# -20210715.net
KiCad netlist of a schematic drawn in Altium Designer
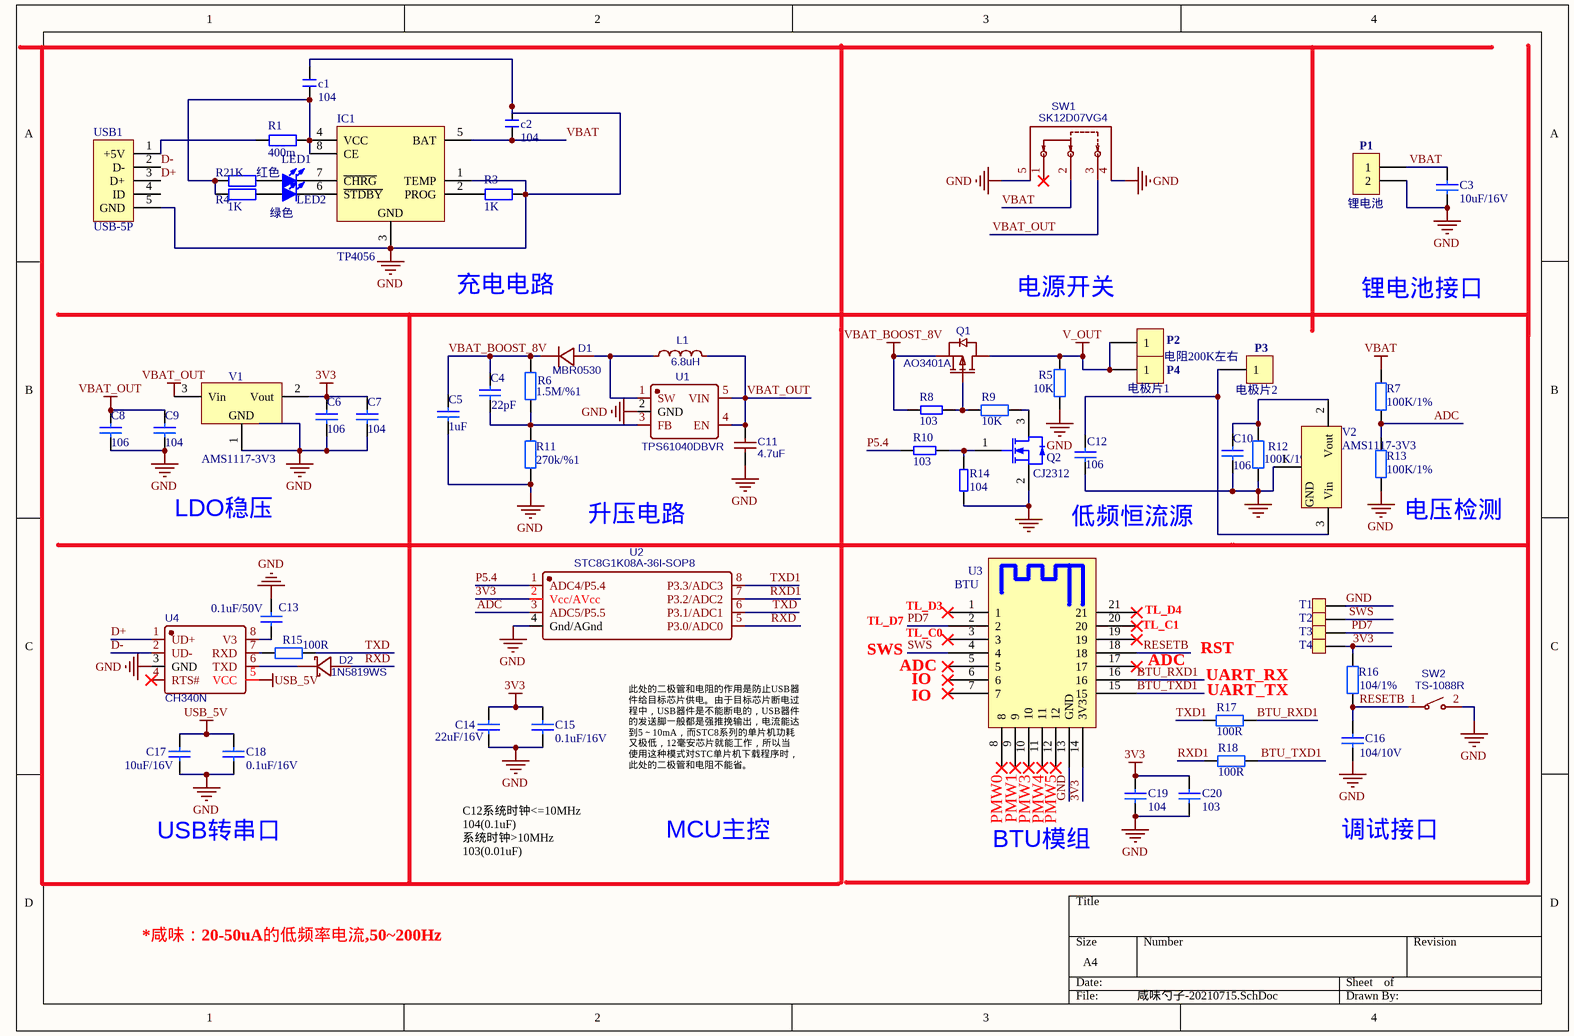
[diagram p0: 咸味勺子-20210715.SchDoc]

(export (version "E")
  (design (tool "Eeschema 10.0.6"))
  (components
    (comp (ref "c1") (value "104") (footprint "C 0805_M") (libsource (lib "Schlib1") (part "0805")))
    (comp (ref "c2") (value "104") (footprint "C 0805_M") (libsource (lib "Schlib1") (part "0805")))
    (comp (ref "C3")
      (value "10uF/16V")
      (footprint "C0603")
      (description "无极性电容")
      (fields (field (name "PART NUMBER") "1.02.05.00869"))
      (libsource (lib "Database_Libs4") (part "Capacitor - non polarized"))
    )
    (comp (ref "C4")
      (value "22pF")
      (footprint "C0402_GRM15")
      (description "无极性电容")
      (fields (field (name "PART NUMBER") "1.02.05.00869"))
      (libsource (lib "Database_Libs4") (part "Capacitor - non polarized"))
    )
    (comp (ref "C5")
      (value "1uF")
      (footprint "C0603")
      (description "无极性电容")
      (fields (field (name "PART NUMBER") "1.02.05.00869"))
      (libsource (lib "Database_Libs4") (part "Capacitor - non polarized"))
    )
    (comp (ref "C6")
      (value "106")
      (footprint "C0603")
      (description "无极性电容")
      (fields (field (name "PART NUMBER") "1.02.05.00869"))
      (libsource (lib "Database_Libs4") (part "Capacitor - non polarized"))
    )
    (comp (ref "C7")
      (value "104")
      (footprint "C0402_GRM15")
      (description "无极性电容")
      (fields (field (name "PART NUMBER") "1.02.05.00869"))
      (libsource (lib "Database_Libs4") (part "Capacitor - non polarized"))
    )
    (comp (ref "C8")
      (value "106")
      (footprint "C0603")
      (description "无极性电容")
      (fields (field (name "PART NUMBER") "1.02.05.00869"))
      (libsource (lib "Database_Libs4") (part "Capacitor - non polarized"))
    )
    (comp (ref "C9")
      (value "104")
      (footprint "C0402_GRM15")
      (description "无极性电容")
      (fields (field (name "PART NUMBER") "1.02.05.00869"))
      (libsource (lib "Database_Libs4") (part "Capacitor - non polarized"))
    )
    (comp (ref "C10")
      (value "106")
      (footprint "C0603")
      (description "无极性电容")
      (fields (field (name "PART NUMBER") "1.02.05.00869"))
      (libsource (lib "Database_Libs4") (part "Capacitor - non polarized"))
    )
    (comp (ref "C11")
      (value "4.7uF")
      (footprint "JMK212BJ475KG-T")
      (fields
        (field (name "BOM_MANUFACTURER PART") "JMK212BJ475KG-T")
        (field (name "BOM_SUPPLIER PART") "C92788")
      )
      (libsource (lib "altium-import") (part "root_1_4.7uF_"))
    )
    (comp (ref "C12")
      (value "106")
      (footprint "C0603")
      (description "无极性电容")
      (fields (field (name "PART NUMBER") "1.02.05.00869"))
      (libsource (lib "Database_Libs4") (part "Capacitor - non polarized"))
    )
    (comp (ref "C13")
      (value "0.1uF/50V")
      (footprint "C0402_GRM15")
      (description "无极性电容")
      (fields (field (name "PART NUMBER") "1.02.05.00834") (field (name "修改人") "system"))
      (libsource (lib "Database_Libs") (part "Capacitor - non polarized"))
    )
    (comp (ref "C14")
      (value "22uF/16V")
      (footprint "C0603")
      (description "无极性电容")
      (fields (field (name "PART NUMBER") "1.02.03.00181") (field (name "修改人") "system"))
      (libsource (lib "Database_Libs") (part "Capacitor - non polarized"))
    )
    (comp (ref "C15")
      (value "0.1uF/16V")
      (footprint "C0402_GRM15")
      (description "无极性电容")
      (fields (field (name "PART NUMBER") "1.02.05.00834") (field (name "修改人") "system"))
      (libsource (lib "Database_Libs") (part "Capacitor - non polarized"))
    )
    (comp (ref "C16")
      (value "104/10V")
      (footprint "C0402_GRM15")
      (description "无极性电容")
      (fields (field (name "PART NUMBER") "1.02.05.00869"))
      (libsource (lib "Database_Libs4") (part "Capacitor - non polarized"))
    )
    (comp (ref "C17")
      (value "10uF/16V")
      (footprint "C0603")
      (description "无极性电容")
      (fields (field (name "PART NUMBER") "1.02.03.00181") (field (name "修改人") "system"))
      (libsource (lib "Database_Libs") (part "Capacitor - non polarized"))
    )
    (comp (ref "C18")
      (value "0.1uF/16V")
      (footprint "C0402_GRM15")
      (description "无极性电容")
      (fields (field (name "PART NUMBER") "1.02.05.00834") (field (name "修改人") "system"))
      (libsource (lib "Database_Libs") (part "Capacitor - non polarized"))
    )
    (comp (ref "C19")
      (value "104")
      (footprint "C0402_GRM15")
      (description "无极性电容")
      (fields (field (name "PART NUMBER") "1.02.05.00869"))
      (libsource (lib "Database_Libs4") (part "Capacitor - non polarized"))
    )
    (comp (ref "C20")
      (value "103")
      (footprint "C0402_GRM15")
      (description "无极性电容")
      (fields (field (name "PART NUMBER") "1.02.05.00869"))
      (libsource (lib "Database_Libs4") (part "Capacitor - non polarized"))
    )
    (comp (ref "D1")
      (value "MBR0530")
      (footprint "MBR0530")
      (fields (field (name "BOM_SUPPLIER PART") "C475718") (field (name "CONTRIBUTOR") "LCSC"))
      (libsource (lib "altium-import") (part "root_0_MBR0530_C475718_"))
    )
    (comp (ref "D2")
      (value "1N5819WS")
      (footprint "1N5819WS")
      (fields (field (name "BOM_SUPPLIER PART") "C1884554") (field (name "CONTRIBUTOR") "LCSC"))
      (libsource (lib "altium-import") (part "root_0_1N5819WS_C1884554_"))
    )
    (comp (ref "IC1") (value "TP4056") (footprint "SOP8_M") (libsource (lib "Schlib1") (part "TP4056")))
    (comp (ref "L1")
      (value "6.8uH")
      (footprint "CDRH3D23NP-6R8PC")
      (fields
        (field (name "BOM_SUPPLIER PART") "C323532")
        (field (name "BOM_MANUFACTURER PART") "CDRH3D23NP-6R8PC")
        (field (name "CONTRIBUTOR") "LCSC")
      )
      (libsource (lib "altium-import") (part "root_0_6.8uH_"))
    )
    (comp (ref "LED1")
      (value "红色")
      (footprint "LED 0805B")
      (description "贴片LED")
      (libsource (lib "Schlib1") (part "LED-SMD"))
    )
    (comp (ref "LED2")
      (value "绿色")
      (footprint "LED 0805B")
      (description "贴片LED")
      (libsource (lib "Schlib1") (part "LED-SMD"))
    )
    (comp (ref "P1")
      (value "锂电池")
      (footprint "1.5mm 2p接插件")
      (description "Connector")
      (libsource (lib "*") (part "CON2"))
    )
    (comp (ref "P2") (value "CON1") (footprint "焊点1") (libsource (lib "智能烧水壶 -电源板") (part "CON1")))
    (comp (ref "P3") (value "CON1") (footprint "焊点1") (libsource (lib "智能烧水壶 -电源板") (part "CON1")))
    (comp (ref "P4") (value "CON1") (footprint "焊点1") (libsource (lib "智能烧水壶 -电源板") (part "CON1")))
    (comp (ref "Q1")
      (value "AO3401A")
      (footprint "AO3401A")
      (fields (field (name "BOM_SUPPLIER PART") "C700954") (field (name "CONTRIBUTOR") "LCSC"))
      (libsource (lib "altium-import") (part "root_1_mirrored_AO3401A_C700954_"))
    )
    (comp (ref "Q2")
      (value "CJ2312")
      (footprint "CJ2312")
      (description "N-Channel MOSFET")
      (fields
        (field (name "PART NUMBER") "1.06.11.00008")
        (field (name "ORCAD LIBRARY PATH") "‪Z:\\tuya_lib\\sch-lib\\DISCRETE.OLB")
        (field (name "修改人") "system")
      )
      (libsource (lib "Database_Libs") (part "MOSFET-N"))
    )
    (comp (ref "R1")
      (value "400m")
      (footprint "R 1210_M")
      (description "贴片电阻")
      (libsource (lib "Schlib1") (part "1812"))
    )
    (comp (ref "R2")
      (value "1K")
      (footprint "R 0805_M")
      (description "贴片电阻")
      (libsource (lib "Schlib1") (part "0805-1"))
    )
    (comp (ref "R3")
      (value "1K")
      (footprint "R 0805_M")
      (description "贴片电阻")
      (libsource (lib "Schlib1") (part "0805-1"))
    )
    (comp (ref "R4")
      (value "1K")
      (footprint "R 0805_M")
      (description "贴片电阻")
      (libsource (lib "Schlib1") (part "0805-1"))
    )
    (comp (ref "R5")
      (value "10K")
      (footprint "R0402")
      (description "电阻")
      (libsource (lib "") (part "Resistor_2"))
    )
    (comp (ref "R6")
      (value "1.5M/%1")
      (footprint "R0402")
      (description "电阻")
      (libsource (lib "") (part "Resistor_1"))
    )
    (comp (ref "R7")
      (value "100K/1%")
      (footprint "R0402")
      (description "电阻")
      (libsource (lib "") (part "Resistor_1"))
    )
    (comp (ref "R8")
      (value "103")
      (footprint "R0402")
      (description "RES")
      (libsource (lib "先锋器件封装库") (part "RES-1"))
    )
    (comp (ref "R9")
      (value "10K")
      (footprint "R0402")
      (description "电阻")
      (libsource (lib "Database_Libs") (part "Resistor"))
    )
    (comp (ref "R10")
      (value "103")
      (footprint "R0402")
      (description "RES")
      (libsource (lib "先锋器件封装库") (part "RES-1"))
    )
    (comp (ref "R11")
      (value "270k/%1")
      (footprint "R0402")
      (description "电阻")
      (libsource (lib "") (part "Resistor_1"))
    )
    (comp (ref "R12")
      (value "100K/1%")
      (footprint "R0402")
      (description "电阻")
      (libsource (lib "") (part "Resistor_1"))
    )
    (comp (ref "R13")
      (value "100K/1%")
      (footprint "R0402")
      (description "电阻")
      (libsource (lib "") (part "Resistor_1"))
    )
    (comp (ref "R14")
      (value "104")
      (footprint "R0402")
      (description "RES")
      (libsource (lib "先锋器件封装库") (part "RES-1"))
    )
    (comp (ref "R15")
      (value "100R")
      (footprint "R0402")
      (description "电阻")
      (fields (field (name "PART NUMBER") "1.01.01.00808") (field (name "修改人") "system"))
      (libsource (lib "Database_Libs") (part "Resistor"))
    )
    (comp (ref "R16")
      (value "104/1%")
      (footprint "R0402")
      (description "电阻")
      (fields (field (name "PART NUMBER") "1.01.01.00808"))
      (libsource (lib "Database_Libs4") (part "Resistor"))
    )
    (comp (ref "R17")
      (value "100R")
      (footprint "R0402")
      (description "电阻")
      (fields (field (name "PART NUMBER") "1.01.01.00808"))
      (libsource (lib "") (part "Resistor_1"))
    )
    (comp (ref "R18")
      (value "100R")
      (footprint "R0402")
      (description "电阻")
      (fields (field (name "PART NUMBER") "1.01.01.00808"))
      (libsource (lib "") (part "Resistor_1"))
    )
    (comp (ref "SW1")
      (value "SK12D07VG4")
      (footprint "SK12D07VG4")
      (fields (field (name "BOM_SUPPLIER PART") "C393937") (field (name "CONTRIBUTOR") "LCSC"))
      (libsource (lib "altium-import") (part "root_0_SK12D07VG4_"))
    )
    (comp (ref "SW2")
      (value "TS-1088R")
      (footprint "TS-1088R-02026")
      (fields
        (field (name "BOM_SUPPLIER PART") "C455280")
        (field (name "BOM_MANUFACTURER PART") "TS-1088R-02026")
        (field (name "CONTRIBUTOR") "LCSC")
      )
      (libsource (lib "altium-import") (part "root_0_TS-1088R-02026_"))
    )
    (comp (ref "T1") (value "TP") (footprint "TP1") (libsource (lib "MIAXIS-SCH") (part "TP")))
    (comp (ref "T2") (value "TP") (footprint "TP1") (libsource (lib "MIAXIS-SCH") (part "TP")))
    (comp (ref "T3") (value "TP") (footprint "TP1") (libsource (lib "MIAXIS-SCH") (part "TP")))
    (comp (ref "T4") (value "TP") (footprint "TP1") (libsource (lib "MIAXIS-SCH") (part "TP")))
    (comp (ref "U1")
      (value "TPS61040DBVR")
      (footprint "TPS61040DBVR")
      (fields (field (name "BOM_SUPPLIER PART") "C7722"))
      (libsource (lib "altium-import") (part "root_0_TPS61040DBVR_"))
    )
    (comp (ref "U2")
      (value "STC8G1K08A-36I-SOP8")
      (footprint "STC8G1K08A-36I-SOP8")
      (fields (field (name "BOM_SUPPLIER PART") "C915663") (field (name "CONTRIBUTOR") "LCSC"))
      (libsource (lib "altium-import") (part "root_0_STC8G1K08A-36I-SOP8_"))
    )
    (comp (ref "U3")
      (value "BTU")
      (footprint "CBU1")
      (fields (field (name "PART NUMBER") "0110"))
      (libsource (lib "BTU_V100") (part "CBU"))
    )
    (comp (ref "U4")
      (value "CH340N")
      (footprint "CH340N")
      (fields (field (name "BOM_SUPPLIER PART") "C506813") (field (name "CONTRIBUTOR") "LCSC"))
      (libsource (lib "TY") (part "CH340N"))
    )
    (comp (ref "USB1")
      (value "USB-5P")
      (footprint "USB-MICRO_A")
      (description "微型USB母座")
      (libsource (lib "常用") (part "USB-5P"))
    )
    (comp (ref "V1") (value "AMS1117-3V3") (footprint "SOT89_M") (libsource (lib "常用") (part "AMS1117")))
    (comp (ref "V2") (value "AMS1117-3V3") (footprint "SOT89_M") (libsource (lib "常用") (part "AMS1117")))
  )
  (nets
    (net (code "1") (name "/ADC") (class "Default")
      (node (ref "R13") (pin "2") (pinfunction "2_2") (pintype "passive"))
      (node (ref "R7") (pin "1") (pinfunction "1_1") (pintype "passive"))
      (node (ref "U2") (pin "3") (pinfunction "ADC5/P5.5_3") (pintype "passive"))
    )
    (net (code "2") (name "/BTU_RXD1") (class "Default")
      (node (ref "R17") (pin "1") (pinfunction "1_1") (pintype "passive"))
      (node (ref "U3") (pin "16") (pinfunction "16_16") (pintype "passive"))
    )
    (net (code "3") (name "/BTU_TXD1") (class "Default")
      (node (ref "R18") (pin "1") (pinfunction "1_1") (pintype "passive"))
      (node (ref "U3") (pin "15") (pinfunction "15_15") (pintype "passive"))
    )
    (net (code "4") (name "/D+") (class "Default")
      (node (ref "U4") (pin "1") (pinfunction "UD+_1") (pintype "passive"))
      (node (ref "USB1") (pin "3") (pinfunction "D+_3") (pintype "passive"))
    )
    (net (code "5") (name "/D-") (class "Default")
      (node (ref "U4") (pin "2") (pinfunction "UD-_2") (pintype "passive"))
      (node (ref "USB1") (pin "2") (pinfunction "D-_2") (pintype "passive"))
    )
    (net (code "6") (name "/P5.4") (class "Default")
      (node (ref "R10") (pin "1") (pintype "passive"))
      (node (ref "U2") (pin "1") (pinfunction "ADC4/P5.4_1") (pintype "passive"))
    )
    (net (code "7") (name "/PD7") (class "Default")
      (node (ref "T3") (pin "1") (pinfunction "1_1") (pintype "passive"))
      (node (ref "U3") (pin "2") (pinfunction "2_2") (pintype "passive"))
    )
    (net (code "8") (name "/RESETB") (class "Default")
      (node (ref "C16") (pin "1") (pinfunction "1_1") (pintype "passive"))
      (node (ref "R16") (pin "1") (pinfunction "1_1") (pintype "passive"))
      (node (ref "SW2") (pin "1") (pinfunction "1_1") (pintype "passive"))
      (node (ref "U3") (pin "18") (pinfunction "18_18") (pintype "passive"))
    )
    (net (code "9") (name "/RXD") (class "Default")
      (node (ref "D2") (pin "2") (pinfunction "A_2") (pintype "passive"))
      (node (ref "U2") (pin "5") (pinfunction "P3.0/ADC0_5") (pintype "passive"))
    )
    (net (code "10") (name "/RXD1") (class "Default")
      (node (ref "R18") (pin "2") (pinfunction "2_2") (pintype "passive"))
      (node (ref "U2") (pin "7") (pinfunction "P3.2/ADC2_7") (pintype "passive"))
    )
    (net (code "11") (name "/SWS") (class "Default")
      (node (ref "T2") (pin "1") (pinfunction "1_1") (pintype "passive"))
      (node (ref "U3") (pin "4") (pinfunction "4_4") (pintype "passive"))
    )
    (net (code "12") (name "/TXD") (class "Default")
      (node (ref "R15") (pin "2") (pinfunction "2_2") (pintype "passive"))
      (node (ref "U2") (pin "6") (pinfunction "P3.1/ADC1_6") (pintype "passive"))
    )
    (net (code "13") (name "/TXD1") (class "Default")
      (node (ref "R17") (pin "2") (pinfunction "2_2") (pintype "passive"))
      (node (ref "U2") (pin "8") (pinfunction "P3.3/ADC3_8") (pintype "passive"))
    )
    (net (code "14") (name "3V3") (class "Default")
      (node (ref "C14") (pin "2") (pinfunction "2_2") (pintype "passive"))
      (node (ref "C15") (pin "2") (pinfunction "2_2") (pintype "passive"))
      (node (ref "C19") (pin "1") (pinfunction "1_1") (pintype "passive"))
      (node (ref "C20") (pin "1") (pinfunction "1_1") (pintype "passive"))
      (node (ref "C6") (pin "1") (pinfunction "1_1") (pintype "passive"))
      (node (ref "C7") (pin "1") (pinfunction "1_1") (pintype "passive"))
      (node (ref "R16") (pin "2") (pinfunction "2_2") (pintype "passive"))
      (node (ref "T4") (pin "1") (pinfunction "1_1") (pintype "passive"))
      (node (ref "U2") (pin "2") (pinfunction "Vcc/AVcc_2") (pintype "passive"))
      (node (ref "U3") (pin "14") (pinfunction "3V3_14") (pintype "passive"))
      (node (ref "V1") (pin "2") (pinfunction "Vout_2") (pintype "passive"))
    )
    (net (code "15") (name "GND") (class "Default")
      (node (ref "C10") (pin "2") (pinfunction "2_2") (pintype "passive"))
      (node (ref "C11") (pin "1") (pinfunction "1_1") (pintype "passive"))
      (node (ref "C12") (pin "2") (pinfunction "2_2") (pintype "passive"))
      (node (ref "C13") (pin "2") (pinfunction "2_2") (pintype "passive"))
      (node (ref "C14") (pin "1") (pinfunction "1_1") (pintype "passive"))
      (node (ref "C15") (pin "1") (pinfunction "1_1") (pintype "passive"))
      (node (ref "C16") (pin "2") (pinfunction "2_2") (pintype "passive"))
      (node (ref "C17") (pin "1") (pinfunction "1_1") (pintype "passive"))
      (node (ref "C18") (pin "1") (pinfunction "1_1") (pintype "passive"))
      (node (ref "C19") (pin "2") (pinfunction "2_2") (pintype "passive"))
      (node (ref "C20") (pin "2") (pinfunction "2_2") (pintype "passive"))
      (node (ref "C3") (pin "2") (pinfunction "2_2") (pintype "passive"))
      (node (ref "C5") (pin "2") (pinfunction "2_2") (pintype "passive"))
      (node (ref "C6") (pin "2") (pinfunction "2_2") (pintype "passive"))
      (node (ref "C7") (pin "2") (pinfunction "2_2") (pintype "passive"))
      (node (ref "C8") (pin "2") (pinfunction "2_2") (pintype "passive"))
      (node (ref "C9") (pin "2") (pinfunction "2_2") (pintype "passive"))
      (node (ref "IC1") (pin "1") (pinfunction "TEMP_1") (pintype "passive"))
      (node (ref "IC1") (pin "3") (pinfunction "GND_3") (pintype "passive"))
      (node (ref "P1") (pin "2") (pinfunction "2_2") (pintype "passive"))
      (node (ref "Q2") (pin "2") (pinfunction "S_2") (pintype "passive"))
      (node (ref "R11") (pin "1") (pinfunction "1_1") (pintype "passive"))
      (node (ref "R12") (pin "1") (pinfunction "1_1") (pintype "passive"))
      (node (ref "R13") (pin "1") (pinfunction "1_1") (pintype "passive"))
      (node (ref "R14") (pin "1") (pintype "passive"))
      (node (ref "R3") (pin "2") (pinfunction "2_2") (pintype "passive"))
      (node (ref "R5") (pin "2") (pinfunction "2_2") (pintype "passive"))
      (node (ref "SW1") (pin "4") (pinfunction "4_4") (pintype "passive"))
      (node (ref "SW1") (pin "5") (pinfunction "5_5") (pintype "passive"))
      (node (ref "SW2") (pin "2") (pinfunction "2_2") (pintype "passive"))
      (node (ref "T1") (pin "1") (pinfunction "1_1") (pintype "passive"))
      (node (ref "U1") (pin "2") (pinfunction "GND_2") (pintype "passive"))
      (node (ref "U2") (pin "4") (pinfunction "Gnd/AGnd_4") (pintype "passive"))
      (node (ref "U3") (pin "13") (pinfunction "GND_13") (pintype "passive"))
      (node (ref "U4") (pin "3") (pinfunction "GND_3") (pintype "passive"))
      (node (ref "USB1") (pin "5") (pinfunction "GND_5") (pintype "passive"))
      (node (ref "V1") (pin "1") (pinfunction "GND_1") (pintype "passive"))
      (node (ref "V2") (pin "1") (pinfunction "GND_1") (pintype "passive"))
      (node (ref "c1") (pin "2") (pinfunction "2_2") (pintype "passive"))
      (node (ref "c2") (pin "2") (pinfunction "2_2") (pintype "passive"))
    )
    (net (code "16") (name "Net-(D1-A)") (class "Default")
      (node (ref "D1") (pin "2") (pinfunction "A_2") (pintype "passive"))
      (node (ref "L1") (pin "1") (pinfunction "1_1") (pintype "passive"))
      (node (ref "U1") (pin "1") (pinfunction "SW_1") (pintype "passive"))
    )
    (net (code "17") (name "Net-(D2-C)") (class "Default")
      (node (ref "D2") (pin "1") (pinfunction "C_1") (pintype "passive"))
      (node (ref "U4") (pin "6") (pinfunction "TXD_6") (pintype "passive"))
    )
    (net (code "18") (name "Net-(IC1-CE)") (class "Default")
      (node (ref "IC1") (pin "4") (pinfunction "VCC_4") (pintype "passive"))
      (node (ref "IC1") (pin "8") (pinfunction "CE_8") (pintype "passive"))
      (node (ref "R1") (pin "2") (pinfunction "2_2") (pintype "passive"))
      (node (ref "R2") (pin "1") (pinfunction "1_1") (pintype "passive"))
      (node (ref "R4") (pin "1") (pinfunction "1_1") (pintype "passive"))
      (node (ref "c1") (pin "1") (pinfunction "1_1") (pintype "passive"))
    )
    (net (code "19") (name "Net-(IC1-PROG)") (class "Default")
      (node (ref "IC1") (pin "2") (pinfunction "PROG_2") (pintype "passive"))
      (node (ref "R3") (pin "1") (pinfunction "1_1") (pintype "passive"))
    )
    (net (code "20") (name "Net-(IC1-~{CHRG})") (class "Default")
      (node (ref "IC1") (pin "7") (pinfunction "~{CHRG}_7") (pintype "passive"))
      (node (ref "LED1") (pin "2") (pinfunction "K_2") (pintype "passive"))
    )
    (net (code "21") (name "Net-(IC1-~{STDBY})") (class "Default")
      (node (ref "IC1") (pin "6") (pinfunction "~{STDBY}_6") (pintype "passive"))
      (node (ref "LED2") (pin "2") (pinfunction "K_2") (pintype "passive"))
    )
    (net (code "22") (name "Net-(LED1-A)") (class "Default")
      (node (ref "LED1") (pin "1") (pinfunction "A_1") (pintype "passive"))
      (node (ref "R2") (pin "2") (pinfunction "2_2") (pintype "passive"))
    )
    (net (code "23") (name "Net-(LED2-A)") (class "Default")
      (node (ref "LED2") (pin "1") (pinfunction "A_1") (pintype "passive"))
      (node (ref "R4") (pin "2") (pinfunction "2_2") (pintype "passive"))
    )
    (net (code "24") (name "Net-(Q1-G)") (class "Default")
      (node (ref "Q1") (pin "1") (pinfunction "G_1") (pintype "passive"))
      (node (ref "R8") (pin "2") (pintype "passive"))
      (node (ref "R9") (pin "1") (pinfunction "1_1") (pintype "passive"))
    )
    (net (code "25") (name "Net-(Q2-D)") (class "Default")
      (node (ref "Q2") (pin "3") (pinfunction "D_3") (pintype "passive"))
      (node (ref "R9") (pin "2") (pinfunction "2_2") (pintype "passive"))
    )
    (net (code "26") (name "Net-(Q2-G)") (class "Default")
      (node (ref "Q2") (pin "1") (pinfunction "G_1") (pintype "passive"))
      (node (ref "R10") (pin "2") (pintype "passive"))
      (node (ref "R14") (pin "2") (pintype "passive"))
    )
    (net (code "27") (name "Net-(U1-FB)") (class "Default")
      (node (ref "C4") (pin "2") (pinfunction "2_2") (pintype "passive"))
      (node (ref "R11") (pin "2") (pinfunction "2_2") (pintype "passive"))
      (node (ref "R6") (pin "1") (pinfunction "1_1") (pintype "passive"))
      (node (ref "U1") (pin "3") (pinfunction "FB_3") (pintype "passive"))
    )
    (net (code "28") (name "Net-(U4-RXD)") (class "Default")
      (node (ref "R15") (pin "1") (pinfunction "1_1") (pintype "passive"))
      (node (ref "U4") (pin "7") (pinfunction "RXD_7") (pintype "passive"))
    )
    (net (code "29") (name "Net-(U4-V3)") (class "Default")
      (node (ref "C13") (pin "1") (pinfunction "1_1") (pintype "passive"))
      (node (ref "U4") (pin "8") (pinfunction "V3_8") (pintype "passive"))
    )
    (net (code "30") (name "Net-(USB1-+5V)") (class "Default")
      (node (ref "R1") (pin "1") (pinfunction "1_1") (pintype "passive"))
      (node (ref "USB1") (pin "1") (pinfunction "+5V_1") (pintype "passive"))
    )
    (net (code "31") (name "Net-(V2-Vin)") (class "Default")
      (node (ref "C12") (pin "1") (pinfunction "1_1") (pintype "passive"))
      (node (ref "P3") (pin "1") (pinfunction "1_1") (pintype "passive"))
      (node (ref "V2") (pin "3") (pinfunction "Vin_3") (pintype "passive"))
    )
    (net (code "32") (name "Net-(V2-Vout)") (class "Default")
      (node (ref "C10") (pin "1") (pinfunction "1_1") (pintype "passive"))
      (node (ref "R12") (pin "2") (pinfunction "2_2") (pintype "passive"))
      (node (ref "V2") (pin "2") (pinfunction "Vout_2") (pintype "passive"))
    )
    (net (code "33") (name "USB_5V") (class "Default")
      (node (ref "C17") (pin "2") (pinfunction "2_2") (pintype "passive"))
      (node (ref "C18") (pin "2") (pinfunction "2_2") (pintype "passive"))
      (node (ref "U4") (pin "5") (pinfunction "VCC_5") (pintype "passive"))
    )
    (net (code "34") (name "VBAT") (class "Default")
      (node (ref "C3") (pin "1") (pinfunction "1_1") (pintype "passive"))
      (node (ref "IC1") (pin "5") (pinfunction "BAT_5") (pintype "passive"))
      (node (ref "P1") (pin "1") (pinfunction "1_1") (pintype "passive"))
      (node (ref "R7") (pin "2") (pinfunction "2_2") (pintype "passive"))
      (node (ref "SW1") (pin "2") (pinfunction "2_2") (pintype "passive"))
      (node (ref "c2") (pin "1") (pinfunction "1_1") (pintype "passive"))
    )
    (net (code "35") (name "VBAT_BOOST_8V") (class "Default")
      (node (ref "C4") (pin "1") (pinfunction "1_1") (pintype "passive"))
      (node (ref "C5") (pin "1") (pinfunction "1_1") (pintype "passive"))
      (node (ref "D1") (pin "1") (pinfunction "K_1") (pintype "passive"))
      (node (ref "Q1") (pin "2") (pinfunction "S_2") (pintype "passive"))
      (node (ref "R6") (pin "2") (pinfunction "2_2") (pintype "passive"))
      (node (ref "R8") (pin "1") (pintype "passive"))
    )
    (net (code "36") (name "VBAT_OUT") (class "Default")
      (node (ref "C11") (pin "2") (pinfunction "2_2") (pintype "passive"))
      (node (ref "C8") (pin "1") (pinfunction "1_1") (pintype "passive"))
      (node (ref "C9") (pin "1") (pinfunction "1_1") (pintype "passive"))
      (node (ref "L1") (pin "2") (pinfunction "2_2") (pintype "passive"))
      (node (ref "SW1") (pin "3") (pinfunction "3_3") (pintype "passive"))
      (node (ref "U1") (pin "4") (pinfunction "EN_4") (pintype "passive"))
      (node (ref "U1") (pin "5") (pinfunction "VIN_5") (pintype "passive"))
      (node (ref "V1") (pin "3") (pinfunction "Vin_3") (pintype "passive"))
    )
    (net (code "37") (name "V_OUT") (class "Default")
      (node (ref "P2") (pin "1") (pinfunction "1_1") (pintype "passive"))
      (node (ref "P4") (pin "1") (pinfunction "1_1") (pintype "passive"))
      (node (ref "Q1") (pin "3") (pinfunction "D_3") (pintype "passive"))
      (node (ref "R5") (pin "1") (pinfunction "1_1") (pintype "passive"))
    )
    (net (code "38") (name "unconnected-(SW1-Pad1)") (class "Default")
      (node (ref "SW1") (pin "1") (pinfunction "1_1") (pintype "passive+no_connect"))
    )
    (net (code "39") (name "unconnected-(U3-Pad1)") (class "Default")
      (node (ref "U3") (pin "1") (pinfunction "1_1") (pintype "passive+no_connect"))
    )
    (net (code "40") (name "unconnected-(U3-Pad3)") (class "Default")
      (node (ref "U3") (pin "3") (pinfunction "3_3") (pintype "passive+no_connect"))
    )
    (net (code "41") (name "unconnected-(U3-Pad5)") (class "Default")
      (node (ref "U3") (pin "5") (pinfunction "5_5") (pintype "passive+no_connect"))
    )
    (net (code "42") (name "unconnected-(U3-Pad6)") (class "Default")
      (node (ref "U3") (pin "6") (pinfunction "6_6") (pintype "passive+no_connect"))
    )
    (net (code "43") (name "unconnected-(U3-Pad7)") (class "Default")
      (node (ref "U3") (pin "7") (pinfunction "7_7") (pintype "passive+no_connect"))
    )
    (net (code "44") (name "unconnected-(U3-Pad8)") (class "Default")
      (node (ref "U3") (pin "8") (pinfunction "8_8") (pintype "passive+no_connect"))
    )
    (net (code "45") (name "unconnected-(U3-Pad9)") (class "Default")
      (node (ref "U3") (pin "9") (pinfunction "9_9") (pintype "passive+no_connect"))
    )
    (net (code "46") (name "unconnected-(U3-Pad10)") (class "Default")
      (node (ref "U3") (pin "10") (pinfunction "10_10") (pintype "passive+no_connect"))
    )
    (net (code "47") (name "unconnected-(U3-Pad11)") (class "Default")
      (node (ref "U3") (pin "11") (pinfunction "11_11") (pintype "passive+no_connect"))
    )
    (net (code "48") (name "unconnected-(U3-Pad12)") (class "Default")
      (node (ref "U3") (pin "12") (pinfunction "12_12") (pintype "passive+no_connect"))
    )
    (net (code "49") (name "unconnected-(U3-Pad17)") (class "Default")
      (node (ref "U3") (pin "17") (pinfunction "17_17") (pintype "passive+no_connect"))
    )
    (net (code "50") (name "unconnected-(U3-Pad19)") (class "Default")
      (node (ref "U3") (pin "19") (pinfunction "19_19") (pintype "passive+no_connect"))
    )
    (net (code "51") (name "unconnected-(U3-Pad20)") (class "Default")
      (node (ref "U3") (pin "20") (pinfunction "20_20") (pintype "passive+no_connect"))
    )
    (net (code "52") (name "unconnected-(U3-Pad21)") (class "Default")
      (node (ref "U3") (pin "21") (pinfunction "21_21") (pintype "passive+no_connect"))
    )
    (net (code "53") (name "unconnected-(U4-RTS#-Pad4)") (class "Default")
      (node (ref "U4") (pin "4") (pinfunction "RTS#_4") (pintype "passive+no_connect"))
    )
    (net (code "54") (name "unconnected-(USB1-ID-Pad4)") (class "Default")
      (node (ref "USB1") (pin "4") (pinfunction "ID_4") (pintype "passive"))
    )
  )
)
